# CANBed-FD_M4.net
KiCad netlist of a schematic drawn in EAGLE
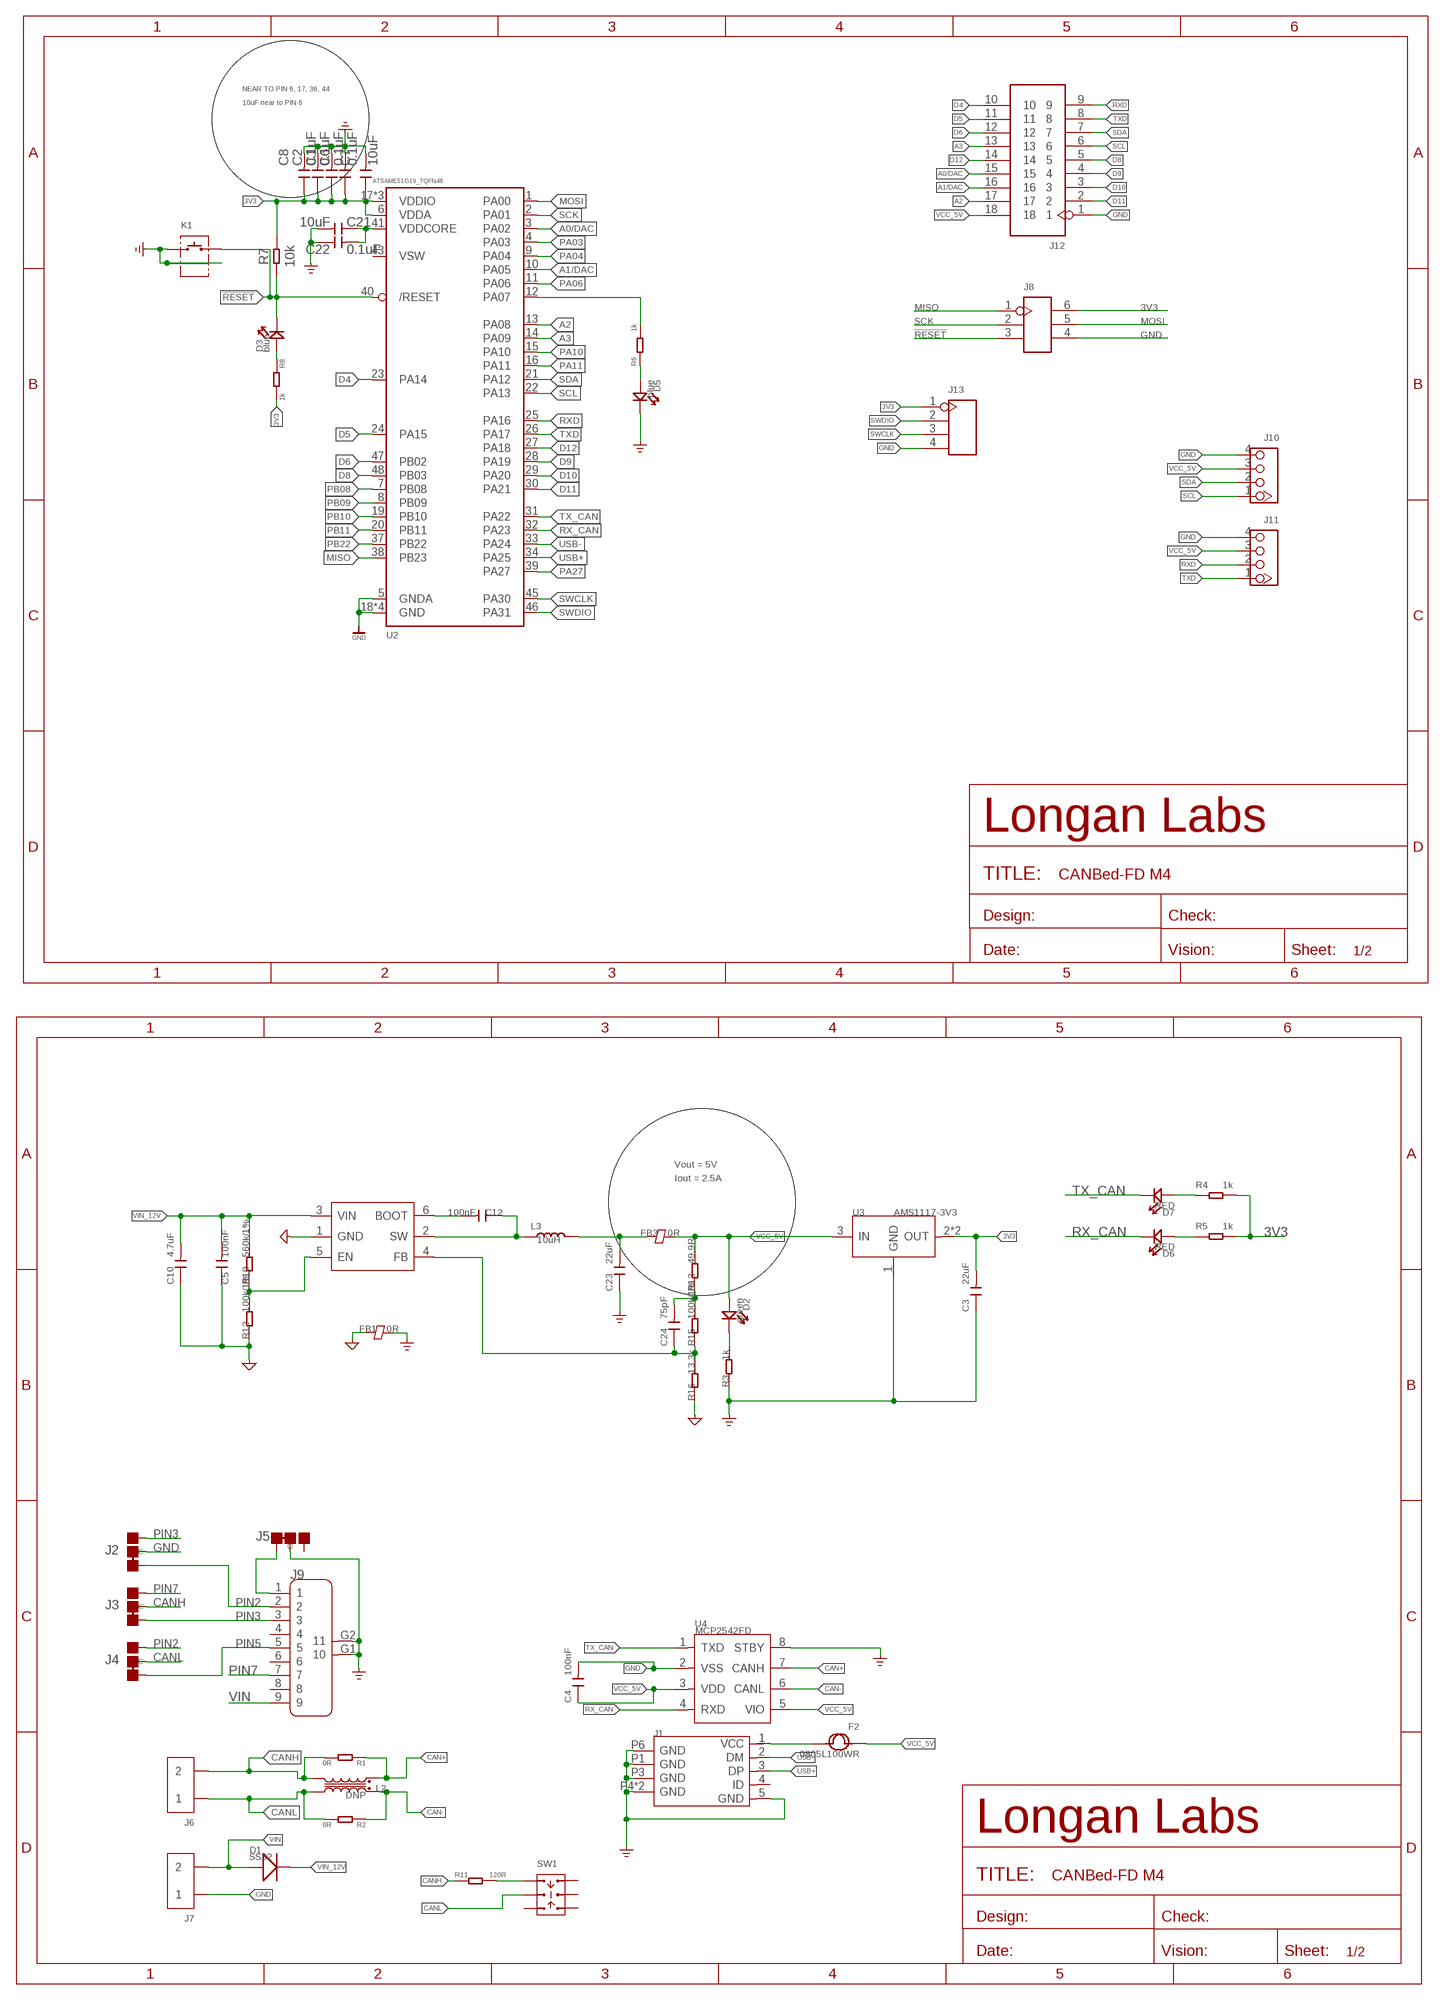
[diagram p0: schematic, sheet 1]

(export (version "E")
  (design (tool "Eeschema 10.0.6"))
  (components
    (comp (ref "C1")
      (value "0.1uF")
      (footprint "eagle-import:C0603")
      (libsource (lib "eagle-import") (part "CAP-0603"))
    )
    (comp (ref "C2")
      (value "0.1uF")
      (footprint "eagle-import:C0603")
      (libsource (lib "eagle-import") (part "CAP-0603"))
    )
    (comp (ref "C3")
      (value "22uF")
      (footprint "eagle-import:C1206")
      (libsource (lib "eagle-import") (part "CAP-1206"))
    )
    (comp (ref "C4")
      (value "100nF")
      (footprint "eagle-import:C0603")
      (libsource (lib "eagle-import") (part "CAP-0603"))
    )
    (comp (ref "C5")
      (value "100nF")
      (footprint "eagle-import:C0603")
      (libsource (lib "eagle-import") (part "CAP-0603"))
    )
    (comp (ref "C6")
      (value "0.1uF")
      (footprint "eagle-import:C0603")
      (libsource (lib "eagle-import") (part "CAP-0603"))
    )
    (comp (ref "C7")
      (value "10uF")
      (footprint "eagle-import:C0603")
      (libsource (lib "eagle-import") (part "CAP-0603"))
    )
    (comp (ref "C8")
      (value "0.1uF")
      (footprint "eagle-import:C0603")
      (libsource (lib "eagle-import") (part "CAP-0603"))
    )
    (comp (ref "C10")
      (value "4.7uF")
      (footprint "eagle-import:C1206")
      (libsource (lib "eagle-import") (part "CAP-1206"))
    )
    (comp (ref "C12")
      (value "100nF")
      (footprint "eagle-import:C0603")
      (libsource (lib "eagle-import") (part "CAP-0603"))
    )
    (comp (ref "C21")
      (value "0.1uF")
      (footprint "eagle-import:C0603")
      (libsource (lib "eagle-import") (part "CAP-0603"))
    )
    (comp (ref "C22")
      (value "10uF")
      (footprint "eagle-import:C0603")
      (libsource (lib "eagle-import") (part "CAP-0603"))
    )
    (comp (ref "C23")
      (value "22uF")
      (footprint "eagle-import:C1206")
      (libsource (lib "eagle-import") (part "CAP-1206"))
    )
    (comp (ref "C24")
      (value "75pF")
      (footprint "eagle-import:C0603")
      (libsource (lib "eagle-import") (part "CAP-0603"))
    )
    (comp (ref "D1")
      (value "SS32")
      (footprint "eagle-import:DO-214AC")
      (libsource (lib "eagle-import") (part "DIODE'SMA'"))
    )
    (comp (ref "D2")
      (value "green")
      (footprint "eagle-import:LED-0603")
      (libsource (lib "eagle-import") (part "LED'0603'"))
    )
    (comp (ref "D3")
      (value "blue")
      (footprint "eagle-import:LED-0603")
      (libsource (lib "eagle-import") (part "LED'0603'"))
    )
    (comp (ref "D5")
      (value "blue")
      (footprint "eagle-import:LED-0603")
      (libsource (lib "eagle-import") (part "LED'0603'"))
    )
    (comp (ref "D6")
      (value "RED")
      (footprint "eagle-import:LED-0603")
      (libsource (lib "eagle-import") (part "LED'0603'"))
    )
    (comp (ref "D7")
      (value "RED")
      (footprint "eagle-import:LED-0603")
      (libsource (lib "eagle-import") (part "LED'0603'"))
    )
    (comp (ref "F2")
      (value "0805L100WR")
      (footprint "eagle-import:F0805")
      (libsource (lib "eagle-import") (part "FUSE0805"))
    )
    (comp (ref "FB1")
      (value "0R")
      (footprint "eagle-import:F0805")
      (libsource (lib "eagle-import") (part "FERRITE-BEAD-0805"))
    )
    (comp (ref "FB3")
      (value "0R")
      (footprint "eagle-import:F0805")
      (libsource (lib "eagle-import") (part "FERRITE-BEAD-0805"))
    )
    (comp (ref "J1")
      (value "MICRO-USB5+4P-320010050")
      (footprint "eagle-import:MICRO-USB5+5P-SMD-0.65-7.2X5.06MM")
      (libsource (lib "eagle-import") (part "MICRO-USB5+4P-320010050"))
    )
    (comp (ref "J2")
      (value "JUMPER-3P-SHORT")
      (footprint "eagle-import:3P-SMD-SHORT")
      (libsource (lib "eagle-import") (part "JUMPER-3P-SHORT"))
    )
    (comp (ref "J3")
      (value "JUMPER-3P-SHORT")
      (footprint "eagle-import:3P-SMD-SHORT")
      (libsource (lib "eagle-import") (part "JUMPER-3P-SHORT"))
    )
    (comp (ref "J4")
      (value "JUMPER-3P-SHORT")
      (footprint "eagle-import:3P-SMD-SHORT")
      (libsource (lib "eagle-import") (part "JUMPER-3P-SHORT"))
    )
    (comp (ref "J5")
      (value "JUMPER-3P-SHORT")
      (footprint "eagle-import:3P-SMD-SHORT")
      (libsource (lib "eagle-import") (part "JUMPER-3P-SHORT"))
    )
    (comp (ref "J6")
      (value "SCREW-TERMINAL-2P'5.08'")
      (footprint "eagle-import:H2-5.0-10.5X8.0MM")
      (libsource (lib "eagle-import") (part "SCREW-TERMINAL-2P'5.08'"))
    )
    (comp (ref "J7")
      (value "SCREW-TERMINAL-2P'5.08'")
      (footprint "eagle-import:H2-5.0-10.5X8.0MM")
      (libsource (lib "eagle-import") (part "SCREW-TERMINAL-2P'5.08'"))
    )
    (comp (ref "J8")
      (value "HEADER-2X3P-2.54")
      (footprint "eagle-import:H2X3-2.54")
      (libsource (lib "eagle-import") (part "HEADER-2X3P-2.54"))
    )
    (comp (ref "J9")
      (value "DB9'MEAL'")
      (footprint "eagle-import:DB9-MEAL")
      (libsource (lib "eagle-import") (part "DB9'MEAL'"))
    )
    (comp (ref "J10")
      (value "320110033")
      (footprint "eagle-import:HW4-2.0")
      (libsource (lib "eagle-import") (part "GROVE-CONNECTOR-DIP-2.0"))
    )
    (comp (ref "J11")
      (value "320110033")
      (footprint "eagle-import:HW4-2.0")
      (libsource (lib "eagle-import") (part "GROVE-CONNECTOR-DIP-2.0"))
    )
    (comp (ref "J12")
      (value "HEADER-2X9P-2.54")
      (footprint "eagle-import:H2X9-2.54")
      (libsource (lib "eagle-import") (part "HEADER-2X9P-2.54"))
    )
    (comp (ref "J13")
      (value "HEADER-4P-65/35MIL")
      (footprint "eagle-import:H4-2.54")
      (libsource (lib "eagle-import") (part "HEADER-4P-65/35MIL"))
    )
    (comp (ref "K1")
      (value "BUTTON-2+2P")
      (footprint "eagle-import:SW2+2P-7.7X2.75X3.95MM")
      (libsource (lib "eagle-import") (part "BUTTON-2+2P"))
    )
    (comp (ref "L2")
      (value "DNP")
      (footprint "eagle-import:INT4-0.85-2X1.25X1.2MM")
      (libsource (lib "eagle-import") (part "INDUCTOR-COMMON-MODE-SRF2012-900YA"))
    )
    (comp (ref "L3")
      (value "10uH")
      (footprint "eagle-import:INT2-SMD-6.6X7.1X3MM")
      (libsource (lib "eagle-import") (part "INDUCTOR-6.6X7.1"))
    )
    (comp (ref "R1")
      (value "0R")
      (footprint "eagle-import:R0603")
      (libsource (lib "eagle-import") (part "RES-0603"))
    )
    (comp (ref "R2")
      (value "0R")
      (footprint "eagle-import:R0603")
      (libsource (lib "eagle-import") (part "RES-0603"))
    )
    (comp (ref "R3")
      (value "1k")
      (footprint "eagle-import:R0603")
      (libsource (lib "eagle-import") (part "RES-0603"))
    )
    (comp (ref "R4")
      (value "1k")
      (footprint "eagle-import:R0603")
      (libsource (lib "eagle-import") (part "RES-0603"))
    )
    (comp (ref "R5")
      (value "1k")
      (footprint "eagle-import:R0603")
      (libsource (lib "eagle-import") (part "RES-0603"))
    )
    (comp (ref "R6")
      (value "1k")
      (footprint "eagle-import:R0603")
      (libsource (lib "eagle-import") (part "RES-0603"))
    )
    (comp (ref "R7")
      (value "10k")
      (footprint "eagle-import:R0603")
      (libsource (lib "eagle-import") (part "RES-0603"))
    )
    (comp (ref "R8")
      (value "1k")
      (footprint "eagle-import:R0603")
      (libsource (lib "eagle-import") (part "RES-0603"))
    )
    (comp (ref "R10")
      (value "560k/1%")
      (footprint "eagle-import:R0603")
      (libsource (lib "eagle-import") (part "RES-0603"))
    )
    (comp (ref "R11")
      (value "120R")
      (footprint "eagle-import:R0603")
      (libsource (lib "eagle-import") (part "RES-0603"))
    )
    (comp (ref "R12")
      (value "100k/1%")
      (footprint "eagle-import:R0603")
      (libsource (lib "eagle-import") (part "RES-0603"))
    )
    (comp (ref "R13")
      (value "49.9R")
      (footprint "eagle-import:R0603")
      (libsource (lib "eagle-import") (part "RES-0603"))
    )
    (comp (ref "R15")
      (value "100k/1%")
      (footprint "eagle-import:R0603")
      (libsource (lib "eagle-import") (part "RES-0603"))
    )
    (comp (ref "R16")
      (value "13.3k")
      (footprint "eagle-import:R0603")
      (libsource (lib "eagle-import") (part "RES-0603"))
    )
    (comp (ref "SW1")
      (value "SWITCH-2CH-6P-311010004")
      (footprint "eagle-import:SW6-2.54-9.0X3.5X3.2+2.0MM")
      (libsource (lib "eagle-import") (part "SWITCH-2CH-6P-311010004"))
    )
    (comp (ref "U1")
      (value "PMIC-TPS54302")
      (footprint "eagle-import:SOT-23-6")
      (libsource (lib "eagle-import") (part "PMIC-TPS54302"))
    )
    (comp (ref "U2")
      (value "ATSAME51G19_TQFN48")
      (footprint "eagle-import:TQFN48_7MM")
      (fields (field (name "MPN") "ATSAME51G19A-MF"))
      (libsource (lib "eagle-import") (part "ATSAME51G19_TQFN48"))
    )
    (comp (ref "U3")
      (value "AMS1117-3V3")
      (footprint "eagle-import:SOT-223")
      (libsource (lib "eagle-import") (part "PMIC-CJ1117S"))
    )
    (comp (ref "U4")
      (value "MCP2542FD")
      (footprint "eagle-import:SOIC8-1.27-5X4MM")
      (libsource (lib "eagle-import") (part "TRANSCEIVER-MCP2542"))
    )
  )
  (nets
    (net (code "1") (name "3V3") (class "Default")
      (node (ref "C1") (pin "1") (pinfunction "1_1") (pintype "passive"))
      (node (ref "C2") (pin "1") (pinfunction "1_1") (pintype "passive"))
      (node (ref "C3") (pin "2") (pinfunction "2_2") (pintype "passive"))
      (node (ref "C6") (pin "1") (pinfunction "1_1") (pintype "passive"))
      (node (ref "C7") (pin "1") (pinfunction "1_1") (pintype "passive"))
      (node (ref "C8") (pin "1") (pinfunction "1_1") (pintype "passive"))
      (node (ref "J13") (pin "1") (pinfunction "P$1_1") (pintype "bidirectional"))
      (node (ref "J8") (pin "6") (pinfunction "6_6") (pintype "bidirectional"))
      (node (ref "R4") (pin "2") (pinfunction "2_2") (pintype "passive"))
      (node (ref "R5") (pin "2") (pinfunction "2_2") (pintype "passive"))
      (node (ref "R7") (pin "2") (pinfunction "2_2") (pintype "passive"))
      (node (ref "R8") (pin "2") (pinfunction "2_2") (pintype "passive"))
      (node (ref "U2") (pin "17") (pinfunction "VDDIO_17") (pintype "passive"))
      (node (ref "U2") (pin "36") (pinfunction "VDDIO_36") (pintype "passive"))
      (node (ref "U2") (pin "44") (pinfunction "VDDIO_44") (pintype "passive"))
      (node (ref "U2") (pin "6") (pinfunction "VDDA_6") (pintype "passive"))
      (node (ref "U3") (pin "2") (pinfunction "OUT_2") (pintype "bidirectional"))
      (node (ref "U3") (pin "TER") (pinfunction "OUT_TER") (pintype "bidirectional"))
    )
    (net (code "2") (name "A0{slash}DAC") (class "Default")
      (node (ref "J12") (pin "15") (pinfunction "15_15") (pintype "bidirectional"))
      (node (ref "U2") (pin "3") (pinfunction "PA02_3") (pintype "bidirectional"))
    )
    (net (code "3") (name "A1{slash}DAC") (class "Default")
      (node (ref "J12") (pin "16") (pinfunction "16_16") (pintype "bidirectional"))
      (node (ref "U2") (pin "10") (pinfunction "PA05_10") (pintype "bidirectional"))
    )
    (net (code "4") (name "A2") (class "Default")
      (node (ref "J12") (pin "17") (pinfunction "17_17") (pintype "bidirectional"))
      (node (ref "U2") (pin "13") (pinfunction "PA08_13") (pintype "bidirectional"))
    )
    (net (code "5") (name "A3") (class "Default")
      (node (ref "J12") (pin "13") (pinfunction "13_13") (pintype "bidirectional"))
      (node (ref "U2") (pin "14") (pinfunction "PA09_14") (pintype "bidirectional"))
    )
    (net (code "6") (name "AGND") (class "Default")
      (node (ref "C10") (pin "1") (pinfunction "1_1") (pintype "passive"))
      (node (ref "C5") (pin "1") (pinfunction "1_1") (pintype "passive"))
      (node (ref "FB1") (pin "1") (pinfunction "1_1") (pintype "bidirectional"))
      (node (ref "R12") (pin "1") (pinfunction "1_1") (pintype "passive"))
      (node (ref "R16") (pin "1") (pinfunction "1_1") (pintype "passive"))
      (node (ref "U1") (pin "1") (pinfunction "GND_1") (pintype "bidirectional"))
    )
    (net (code "7") (name "CAN+") (class "Default")
      (node (ref "L2") (pin "4") (pinfunction "4_4") (pintype "bidirectional"))
      (node (ref "R1") (pin "1") (pinfunction "1_1") (pintype "passive"))
      (node (ref "U4") (pin "7") (pinfunction "CANH_7") (pintype "bidirectional"))
    )
    (net (code "8") (name "CAN-") (class "Default")
      (node (ref "L2") (pin "1") (pinfunction "1_1") (pintype "bidirectional"))
      (node (ref "R2") (pin "1") (pinfunction "1_1") (pintype "passive"))
      (node (ref "U4") (pin "6") (pinfunction "CANL_6") (pintype "bidirectional"))
    )
    (net (code "9") (name "CANH") (class "Default")
      (node (ref "J3") (pin "MM") (pinfunction "C_MM") (pintype "bidirectional"))
      (node (ref "J6") (pin "2") (pinfunction "2_2") (pintype "bidirectional"))
      (node (ref "L2") (pin "3") (pinfunction "3_3") (pintype "bidirectional"))
      (node (ref "R1") (pin "2") (pinfunction "2_2") (pintype "passive"))
      (node (ref "R11") (pin "1") (pinfunction "1_1") (pintype "passive"))
    )
    (net (code "10") (name "CANL") (class "Default")
      (node (ref "J4") (pin "MM") (pinfunction "C_MM") (pintype "bidirectional"))
      (node (ref "J6") (pin "1") (pinfunction "1_1") (pintype "bidirectional"))
      (node (ref "L2") (pin "2") (pinfunction "2_2") (pintype "bidirectional"))
      (node (ref "R2") (pin "2") (pinfunction "2_2") (pintype "passive"))
      (node (ref "SW1") (pin "COM1") (pinfunction "COM1_COM1") (pintype "bidirectional"))
    )
    (net (code "11") (name "D4") (class "Default")
      (node (ref "J12") (pin "10") (pinfunction "10_10") (pintype "bidirectional"))
      (node (ref "U2") (pin "23") (pinfunction "PA14_23") (pintype "bidirectional"))
    )
    (net (code "12") (name "D5") (class "Default")
      (node (ref "J12") (pin "11") (pinfunction "11_11") (pintype "bidirectional"))
      (node (ref "U2") (pin "24") (pinfunction "PA15_24") (pintype "bidirectional"))
    )
    (net (code "13") (name "D6") (class "Default")
      (node (ref "J12") (pin "12") (pinfunction "12_12") (pintype "bidirectional"))
      (node (ref "U2") (pin "47") (pinfunction "PB02_47") (pintype "bidirectional"))
    )
    (net (code "14") (name "D8") (class "Default")
      (node (ref "J12") (pin "5") (pinfunction "5_5") (pintype "bidirectional"))
      (node (ref "U2") (pin "48") (pinfunction "PB03_48") (pintype "bidirectional"))
    )
    (net (code "15") (name "D9") (class "Default")
      (node (ref "J12") (pin "4") (pinfunction "4_4") (pintype "bidirectional"))
      (node (ref "U2") (pin "28") (pinfunction "PA19_28") (pintype "bidirectional"))
    )
    (net (code "16") (name "D10") (class "Default")
      (node (ref "J12") (pin "3") (pinfunction "3_3") (pintype "bidirectional"))
      (node (ref "U2") (pin "29") (pinfunction "PA20_29") (pintype "bidirectional"))
    )
    (net (code "17") (name "D11") (class "Default")
      (node (ref "J12") (pin "2") (pinfunction "2_2") (pintype "bidirectional"))
      (node (ref "U2") (pin "30") (pinfunction "PA21_30") (pintype "bidirectional"))
    )
    (net (code "18") (name "D12") (class "Default")
      (node (ref "J12") (pin "14") (pinfunction "14_14") (pintype "bidirectional"))
      (node (ref "U2") (pin "27") (pinfunction "PA18_27") (pintype "bidirectional"))
    )
    (net (code "19") (name "GND") (class "Default")
      (node (ref "C1") (pin "2") (pinfunction "2_2") (pintype "passive"))
      (node (ref "C2") (pin "2") (pinfunction "2_2") (pintype "passive"))
      (node (ref "C21") (pin "1") (pinfunction "1_1") (pintype "passive"))
      (node (ref "C22") (pin "2") (pinfunction "2_2") (pintype "passive"))
      (node (ref "C23") (pin "1") (pinfunction "1_1") (pintype "passive"))
      (node (ref "C3") (pin "1") (pinfunction "1_1") (pintype "passive"))
      (node (ref "C4") (pin "2") (pinfunction "2_2") (pintype "passive"))
      (node (ref "C6") (pin "2") (pinfunction "2_2") (pintype "passive"))
      (node (ref "C7") (pin "2") (pinfunction "2_2") (pintype "passive"))
      (node (ref "C8") (pin "2") (pinfunction "2_2") (pintype "passive"))
      (node (ref "D5") (pin "-") (pinfunction "-_-") (pintype "passive"))
      (node (ref "FB1") (pin "2") (pinfunction "2_2") (pintype "bidirectional"))
      (node (ref "J1") (pin "5") (pinfunction "GND_5") (pintype "bidirectional"))
      (node (ref "J1") (pin "P1") (pinfunction "GND_P1") (pintype "bidirectional"))
      (node (ref "J1") (pin "P3") (pinfunction "GND_P3") (pintype "bidirectional"))
      (node (ref "J1") (pin "P4") (pinfunction "GND_P4") (pintype "bidirectional"))
      (node (ref "J1") (pin "P5") (pinfunction "GND_P5") (pintype "bidirectional"))
      (node (ref "J1") (pin "P6") (pinfunction "GND_P6") (pintype "bidirectional"))
      (node (ref "J10") (pin "4") (pinfunction "4_4") (pintype "bidirectional"))
      (node (ref "J11") (pin "4") (pinfunction "4_4") (pintype "bidirectional"))
      (node (ref "J12") (pin "1") (pinfunction "1_1") (pintype "bidirectional"))
      (node (ref "J13") (pin "4") (pinfunction "P$4_4") (pintype "bidirectional"))
      (node (ref "J2") (pin "MM") (pinfunction "C_MM") (pintype "bidirectional"))
      (node (ref "J5") (pin "MM") (pinfunction "C_MM") (pintype "bidirectional"))
      (node (ref "J7") (pin "1") (pinfunction "1_1") (pintype "bidirectional"))
      (node (ref "J8") (pin "4") (pinfunction "4_4") (pintype "bidirectional"))
      (node (ref "J9") (pin "G1") (pinfunction "10_G1") (pintype "bidirectional"))
      (node (ref "J9") (pin "G2") (pinfunction "11_G2") (pintype "bidirectional"))
      (node (ref "K1") (pin "1") (pinfunction "1_1") (pintype "bidirectional"))
      (node (ref "K1") (pin "S1") (pinfunction "S1_S1") (pintype "bidirectional"))
      (node (ref "K1") (pin "S2") (pinfunction "S2_S2") (pintype "bidirectional"))
      (node (ref "R3") (pin "1") (pinfunction "1_1") (pintype "passive"))
      (node (ref "U2") (pin "18") (pinfunction "GND_18") (pintype "passive"))
      (node (ref "U2") (pin "35") (pinfunction "GND_35") (pintype "passive"))
      (node (ref "U2") (pin "42") (pinfunction "GND_42") (pintype "passive"))
      (node (ref "U2") (pin "5") (pinfunction "GNDA_5") (pintype "passive"))
      (node (ref "U2") (pin "THERMAL") (pinfunction "GND_THERMAL") (pintype "passive"))
      (node (ref "U3") (pin "1") (pinfunction "GND_1") (pintype "bidirectional"))
      (node (ref "U4") (pin "2") (pinfunction "VSS_2") (pintype "bidirectional"))
      (node (ref "U4") (pin "8") (pinfunction "STBY_8") (pintype "bidirectional"))
    )
    (net (code "20") (name "MISO") (class "Default")
      (node (ref "J8") (pin "1") (pinfunction "1_1") (pintype "bidirectional"))
      (node (ref "U2") (pin "38") (pinfunction "PB23_38") (pintype "bidirectional"))
    )
    (net (code "21") (name "MOSI") (class "Default")
      (node (ref "J8") (pin "5") (pinfunction "5_5") (pintype "bidirectional"))
      (node (ref "U2") (pin "1") (pinfunction "PA00_1") (pintype "bidirectional"))
    )
    (net (code "22") (name "Net-(C23-Pad2)") (class "Default")
      (node (ref "C23") (pin "2") (pinfunction "2_2") (pintype "passive"))
      (node (ref "FB3") (pin "1") (pinfunction "1_1") (pintype "bidirectional"))
      (node (ref "L3") (pin "2") (pinfunction "2_2") (pintype "passive"))
    )
    (net (code "23") (name "Net-(C24-Pad2)") (class "Default")
      (node (ref "C24") (pin "2") (pinfunction "2_2") (pintype "passive"))
      (node (ref "R13") (pin "1") (pinfunction "1_1") (pintype "passive"))
      (node (ref "R15") (pin "2") (pinfunction "2_2") (pintype "passive"))
    )
    (net (code "24") (name "Net-(D2-Pad-)") (class "Default")
      (node (ref "D2") (pin "-") (pinfunction "-_-") (pintype "passive"))
      (node (ref "R3") (pin "2") (pinfunction "2_2") (pintype "passive"))
    )
    (net (code "25") (name "Net-(D3-Pad+)") (class "Default")
      (node (ref "D3") (pin "+") (pinfunction "+_+") (pintype "passive"))
      (node (ref "R8") (pin "1") (pinfunction "1_1") (pintype "passive"))
    )
    (net (code "26") (name "Net-(D5-Pad+)") (class "Default")
      (node (ref "D5") (pin "+") (pinfunction "+_+") (pintype "passive"))
      (node (ref "R6") (pin "1") (pinfunction "1_1") (pintype "passive"))
    )
    (net (code "27") (name "Net-(D6-Pad+)") (class "Default")
      (node (ref "D6") (pin "+") (pinfunction "+_+") (pintype "passive"))
      (node (ref "R5") (pin "1") (pinfunction "1_1") (pintype "passive"))
    )
    (net (code "28") (name "Net-(D7-Pad+)") (class "Default")
      (node (ref "D7") (pin "+") (pinfunction "+_+") (pintype "passive"))
      (node (ref "R4") (pin "1") (pinfunction "1_1") (pintype "passive"))
    )
    (net (code "29") (name "Net-(J1-VCC)") (class "Default")
      (node (ref "F2") (pin "2") (pinfunction "2_2") (pintype "bidirectional"))
      (node (ref "J1") (pin "1") (pinfunction "VCC_1") (pintype "bidirectional"))
    )
    (net (code "30") (name "Net-(J5-L)") (class "Default")
      (node (ref "J5") (pin "11") (pinfunction "L_11") (pintype "bidirectional"))
      (node (ref "J9") (pin "1") (pinfunction "1_1") (pintype "bidirectional"))
    )
    (net (code "31") (name "Net-(R11-Pad2)") (class "Default")
      (node (ref "R11") (pin "2") (pinfunction "2_2") (pintype "passive"))
      (node (ref "SW1") (pin "CH1A") (pinfunction "CH1A_CH1A") (pintype "bidirectional"))
    )
    (net (code "32") (name "Net-(U1-BOOT)") (class "Default")
      (node (ref "C12") (pin "2") (pinfunction "2_2") (pintype "passive"))
      (node (ref "U1") (pin "6") (pinfunction "BOOT_6") (pintype "bidirectional"))
    )
    (net (code "33") (name "Net-(U1-EN)") (class "Default")
      (node (ref "R10") (pin "1") (pinfunction "1_1") (pintype "passive"))
      (node (ref "R12") (pin "2") (pinfunction "2_2") (pintype "passive"))
      (node (ref "U1") (pin "5") (pinfunction "EN_5") (pintype "bidirectional"))
    )
    (net (code "34") (name "Net-(U1-FB)") (class "Default")
      (node (ref "C24") (pin "1") (pinfunction "1_1") (pintype "passive"))
      (node (ref "R15") (pin "1") (pinfunction "1_1") (pintype "passive"))
      (node (ref "R16") (pin "2") (pinfunction "2_2") (pintype "passive"))
      (node (ref "U1") (pin "4") (pinfunction "FB_4") (pintype "bidirectional"))
    )
    (net (code "35") (name "Net-(U1-SW)") (class "Default")
      (node (ref "C12") (pin "1") (pinfunction "1_1") (pintype "passive"))
      (node (ref "L3") (pin "1") (pinfunction "1_1") (pintype "passive"))
      (node (ref "U1") (pin "2") (pinfunction "SW_2") (pintype "bidirectional"))
    )
    (net (code "36") (name "Net-(U2-PA07)") (class "Default")
      (node (ref "R6") (pin "2") (pinfunction "2_2") (pintype "passive"))
      (node (ref "U2") (pin "12") (pinfunction "PA07_12") (pintype "bidirectional"))
    )
    (net (code "37") (name "Net-(U2-VDDCORE)") (class "Default")
      (node (ref "C21") (pin "2") (pinfunction "2_2") (pintype "passive"))
      (node (ref "C22") (pin "1") (pinfunction "1_1") (pintype "passive"))
      (node (ref "U2") (pin "41") (pinfunction "VDDCORE_41") (pintype "passive"))
    )
    (net (code "38") (name "PA03") (class "Default")
      (node (ref "U2") (pin "4") (pinfunction "PA03_4") (pintype "bidirectional"))
    )
    (net (code "39") (name "PA04") (class "Default")
      (node (ref "U2") (pin "9") (pinfunction "PA04_9") (pintype "bidirectional"))
    )
    (net (code "40") (name "PA06") (class "Default")
      (node (ref "U2") (pin "11") (pinfunction "PA06_11") (pintype "bidirectional"))
    )
    (net (code "41") (name "PA10") (class "Default")
      (node (ref "U2") (pin "15") (pinfunction "PA10_15") (pintype "bidirectional"))
    )
    (net (code "42") (name "PA11") (class "Default")
      (node (ref "U2") (pin "16") (pinfunction "PA11_16") (pintype "bidirectional"))
    )
    (net (code "43") (name "PA27") (class "Default")
      (node (ref "U2") (pin "39") (pinfunction "PA27_39") (pintype "bidirectional"))
    )
    (net (code "44") (name "PB08") (class "Default")
      (node (ref "U2") (pin "7") (pinfunction "PB08_7") (pintype "bidirectional"))
    )
    (net (code "45") (name "PB09") (class "Default")
      (node (ref "U2") (pin "8") (pinfunction "PB09_8") (pintype "bidirectional"))
    )
    (net (code "46") (name "PB10") (class "Default")
      (node (ref "U2") (pin "19") (pinfunction "PB10_19") (pintype "bidirectional"))
    )
    (net (code "47") (name "PB11") (class "Default")
      (node (ref "U2") (pin "20") (pinfunction "PB11_20") (pintype "bidirectional"))
    )
    (net (code "48") (name "PB22") (class "Default")
      (node (ref "U2") (pin "37") (pinfunction "PB22_37") (pintype "bidirectional"))
    )
    (net (code "49") (name "PIN2") (class "Default")
      (node (ref "J2") (pin "11") (pinfunction "L_11") (pintype "bidirectional"))
      (node (ref "J4") (pin "00") (pinfunction "R_00") (pintype "bidirectional"))
      (node (ref "J9") (pin "2") (pinfunction "2_2") (pintype "bidirectional"))
    )
    (net (code "50") (name "PIN3") (class "Default")
      (node (ref "J2") (pin "00") (pinfunction "R_00") (pintype "bidirectional"))
      (node (ref "J3") (pin "11") (pinfunction "L_11") (pintype "bidirectional"))
      (node (ref "J9") (pin "3") (pinfunction "3_3") (pintype "bidirectional"))
    )
    (net (code "51") (name "PIN5") (class "Default")
      (node (ref "J4") (pin "11") (pinfunction "L_11") (pintype "bidirectional"))
      (node (ref "J9") (pin "5") (pinfunction "5_5") (pintype "bidirectional"))
    )
    (net (code "52") (name "PIN7") (class "Default")
      (node (ref "J3") (pin "00") (pinfunction "R_00") (pintype "bidirectional"))
      (node (ref "J9") (pin "7") (pinfunction "7_7") (pintype "bidirectional"))
    )
    (net (code "53") (name "RXD") (class "Default")
      (node (ref "J11") (pin "2") (pinfunction "2_2") (pintype "bidirectional"))
      (node (ref "J12") (pin "9") (pinfunction "9_9") (pintype "bidirectional"))
      (node (ref "U2") (pin "25") (pinfunction "PA16_25") (pintype "bidirectional"))
    )
    (net (code "54") (name "RX_CAN") (class "Default")
      (node (ref "D6") (pin "-") (pinfunction "-_-") (pintype "passive"))
      (node (ref "U2") (pin "32") (pinfunction "PA23_32") (pintype "bidirectional"))
      (node (ref "U4") (pin "4") (pinfunction "RXD_4") (pintype "bidirectional"))
    )
    (net (code "55") (name "SCK") (class "Default")
      (node (ref "J8") (pin "2") (pinfunction "2_2") (pintype "bidirectional"))
      (node (ref "U2") (pin "2") (pinfunction "PA01_2") (pintype "bidirectional"))
    )
    (net (code "56") (name "SCL") (class "Default")
      (node (ref "J10") (pin "1") (pinfunction "1_1") (pintype "bidirectional"))
      (node (ref "J12") (pin "6") (pinfunction "6_6") (pintype "bidirectional"))
      (node (ref "U2") (pin "22") (pinfunction "PA13_22") (pintype "bidirectional"))
    )
    (net (code "57") (name "SDA") (class "Default")
      (node (ref "J10") (pin "2") (pinfunction "2_2") (pintype "bidirectional"))
      (node (ref "J12") (pin "7") (pinfunction "7_7") (pintype "bidirectional"))
      (node (ref "U2") (pin "21") (pinfunction "PA12_21") (pintype "bidirectional"))
    )
    (net (code "58") (name "SWCLK") (class "Default")
      (node (ref "J13") (pin "3") (pinfunction "P$3_3") (pintype "bidirectional"))
      (node (ref "U2") (pin "45") (pinfunction "PA30_45") (pintype "bidirectional"))
    )
    (net (code "59") (name "SWDIO") (class "Default")
      (node (ref "J13") (pin "2") (pinfunction "P$2_2") (pintype "bidirectional"))
      (node (ref "U2") (pin "46") (pinfunction "PA31_46") (pintype "bidirectional"))
    )
    (net (code "60") (name "TXD") (class "Default")
      (node (ref "J11") (pin "1") (pinfunction "1_1") (pintype "bidirectional"))
      (node (ref "J12") (pin "8") (pinfunction "8_8") (pintype "bidirectional"))
      (node (ref "U2") (pin "26") (pinfunction "PA17_26") (pintype "bidirectional"))
    )
    (net (code "61") (name "TX_CAN") (class "Default")
      (node (ref "D7") (pin "-") (pinfunction "-_-") (pintype "passive"))
      (node (ref "U2") (pin "31") (pinfunction "PA22_31") (pintype "bidirectional"))
      (node (ref "U4") (pin "1") (pinfunction "TXD_1") (pintype "bidirectional"))
    )
    (net (code "62") (name "USB+") (class "Default")
      (node (ref "J1") (pin "3") (pinfunction "DP_3") (pintype "bidirectional"))
      (node (ref "U2") (pin "34") (pinfunction "PA25_34") (pintype "bidirectional"))
    )
    (net (code "63") (name "USB-") (class "Default")
      (node (ref "J1") (pin "2") (pinfunction "DM_2") (pintype "bidirectional"))
      (node (ref "U2") (pin "33") (pinfunction "PA24_33") (pintype "bidirectional"))
    )
    (net (code "64") (name "VCC_5V") (class "Default")
      (node (ref "C4") (pin "1") (pinfunction "1_1") (pintype "passive"))
      (node (ref "D2") (pin "+") (pinfunction "+_+") (pintype "passive"))
      (node (ref "F2") (pin "1") (pinfunction "1_1") (pintype "bidirectional"))
      (node (ref "FB3") (pin "2") (pinfunction "2_2") (pintype "bidirectional"))
      (node (ref "J10") (pin "3") (pinfunction "3_3") (pintype "bidirectional"))
      (node (ref "J11") (pin "3") (pinfunction "3_3") (pintype "bidirectional"))
      (node (ref "J12") (pin "18") (pinfunction "18_18") (pintype "bidirectional"))
      (node (ref "R13") (pin "2") (pinfunction "2_2") (pintype "passive"))
      (node (ref "U3") (pin "3") (pinfunction "IN_3") (pintype "bidirectional"))
      (node (ref "U4") (pin "3") (pinfunction "VDD_3") (pintype "bidirectional"))
      (node (ref "U4") (pin "5") (pinfunction "VIO_5") (pintype "bidirectional"))
    )
    (net (code "65") (name "VIN") (class "Default")
      (node (ref "D1") (pin "1") (pinfunction "+_1") (pintype "passive"))
      (node (ref "J7") (pin "2") (pinfunction "2_2") (pintype "bidirectional"))
      (node (ref "J9") (pin "9") (pinfunction "9_9") (pintype "bidirectional"))
    )
    (net (code "66") (name "VIN_12V") (class "Default")
      (node (ref "C10") (pin "2") (pinfunction "2_2") (pintype "passive"))
      (node (ref "C5") (pin "2") (pinfunction "2_2") (pintype "passive"))
      (node (ref "D1") (pin "2") (pinfunction "-_2") (pintype "passive"))
      (node (ref "R10") (pin "2") (pinfunction "2_2") (pintype "passive"))
      (node (ref "U1") (pin "3") (pinfunction "VIN_3") (pintype "bidirectional"))
    )
    (net (code "67") (name "unconnected-(J1-ID-Pad4)") (class "Default")
      (node (ref "J1") (pin "4") (pinfunction "ID_4") (pintype "bidirectional"))
    )
    (net (code "68") (name "unconnected-(J5-R-Pad00)") (class "Default")
      (node (ref "J5") (pin "00") (pinfunction "R_00") (pintype "bidirectional"))
    )
    (net (code "69") (name "unconnected-(J9-Pad4)") (class "Default")
      (node (ref "J9") (pin "4") (pinfunction "4_4") (pintype "bidirectional"))
    )
    (net (code "70") (name "unconnected-(J9-Pad6)") (class "Default")
      (node (ref "J9") (pin "6") (pinfunction "6_6") (pintype "bidirectional"))
    )
    (net (code "71") (name "unconnected-(J9-Pad8)") (class "Default")
      (node (ref "J9") (pin "8") (pinfunction "8_8") (pintype "bidirectional"))
    )
    (net (code "72") (name "unconnected-(SW1-PadCH1B)") (class "Default")
      (node (ref "SW1") (pin "CH1B") (pinfunction "CH1B_CH1B") (pintype "bidirectional"))
    )
    (net (code "73") (name "unconnected-(SW1-PadCH2A)") (class "Default")
      (node (ref "SW1") (pin "CH2A") (pinfunction "CH2A_CH2A") (pintype "bidirectional"))
    )
    (net (code "74") (name "unconnected-(SW1-PadCH2B)") (class "Default")
      (node (ref "SW1") (pin "CH2B") (pinfunction "CH2B_CH2B") (pintype "bidirectional"))
    )
    (net (code "75") (name "unconnected-(SW1-PadCOM2)") (class "Default")
      (node (ref "SW1") (pin "COM2") (pinfunction "COM2_COM2") (pintype "bidirectional"))
    )
    (net (code "76") (name "unconnected-(U2-VSW-Pad43)") (class "Default")
      (node (ref "U2") (pin "43") (pinfunction "VSW_43") (pintype "passive"))
    )
    (net (code "77") (name "~{RESET}") (class "Default")
      (node (ref "D3") (pin "-") (pinfunction "-_-") (pintype "passive"))
      (node (ref "J8") (pin "3") (pinfunction "3_3") (pintype "bidirectional"))
      (node (ref "K1") (pin "2") (pinfunction "2_2") (pintype "bidirectional"))
      (node (ref "R7") (pin "1") (pinfunction "1_1") (pintype "passive"))
      (node (ref "U2") (pin "40") (pinfunction "/RESET_40") (pintype "bidirectional"))
    )
  )
)
